# Desktop_Widget_ESP03.net
KiCad netlist of a schematic drawn in EAGLE
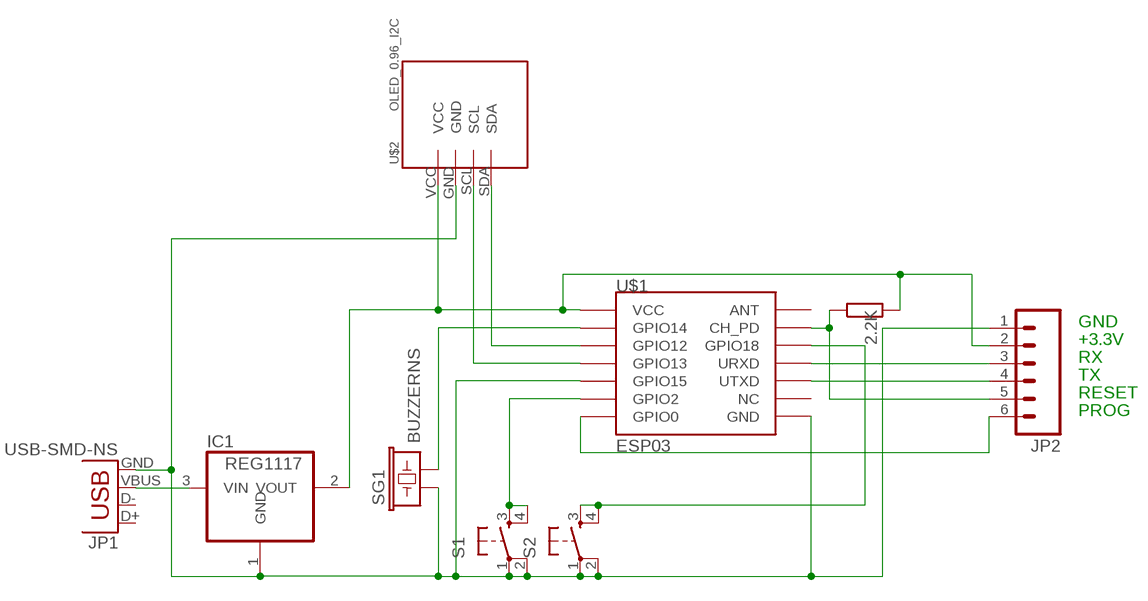
[diagram p0: schematic, sheet 1]

(export (version "E")
  (design (tool "Eeschema 10.0.6"))
  (components
    (comp (ref "IC1")
      (value "REG1117")
      (footprint "eagle-import:SOT223")
      (libsource (lib "eagle-import") (part "REG1117"))
    )
    (comp (ref "JP1")
      (value "USB-SMD-NS")
      (footprint "eagle-import:USB-MINIB-NOSTOP")
      (libsource (lib "eagle-import") (part "USB-SMD-NS"))
    )
    (comp (ref "JP2")
      (value "M06SILK_FEMALE_PTH")
      (footprint "eagle-import:1X06")
      (libsource (lib "eagle-import") (part "M06SILK_FEMALE_PTH"))
    )
    (comp (ref "S1")
      (value "TAC_SWITCHPTH")
      (footprint "eagle-import:TACTILE-PTH")
      (libsource (lib "eagle-import") (part "TAC_SWITCHPTH"))
    )
    (comp (ref "S2")
      (value "TAC_SWITCHPTH")
      (footprint "eagle-import:TACTILE-PTH")
      (libsource (lib "eagle-import") (part "TAC_SWITCHPTH"))
    )
    (comp (ref "SG1")
      (value "BUZZERNS")
      (footprint "eagle-import:BUZZER-12MM-NS")
      (libsource (lib "eagle-import") (part "BUZZERNS"))
    )
    (comp (ref "U$1")
      (value "ESP03")
      (footprint "eagle-import:ESP03")
      (libsource (lib "eagle-import") (part "ESP03"))
    )
    (comp (ref "U$2")
      (value "OLED_0.96_I2C")
      (footprint "eagle-import:OLED_0.96_I2C")
      (libsource (lib "eagle-import") (part "OLED_0.96_I2C"))
    )
  )
  (nets
    (net (code "1") (name "Net-(IC1-GND)") (class "Default")
      (node (ref "IC1") (pin "1") (pinfunction "GND_1") (pintype "power_in"))
      (node (ref "JP1") (pin "GND") (pinfunction "GND_GND") (pintype "bidirectional"))
      (node (ref "JP2") (pin "1") (pinfunction "1_1") (pintype "passive"))
      (node (ref "S1") (pin "1") (pinfunction "1_1") (pintype "passive"))
      (node (ref "S1") (pin "2") (pinfunction "2_2") (pintype "passive"))
      (node (ref "S2") (pin "1") (pinfunction "1_1") (pintype "passive"))
      (node (ref "S2") (pin "2") (pinfunction "2_2") (pintype "passive"))
      (node (ref "SG1") (pin "+") (pinfunction "1_+") (pintype "passive"))
      (node (ref "U$1") (pin "GND") (pinfunction "GND_GND") (pintype "bidirectional"))
      (node (ref "U$1") (pin "GPIO15") (pinfunction "GPIO15_GPIO15") (pintype "bidirectional"))
      (node (ref "U$2") (pin "GND") (pinfunction "GND_GND") (pintype "bidirectional"))
    )
    (net (code "2") (name "Net-(IC1-VOUT)") (class "Default")
      (node (ref "IC1") (pin "2") (pinfunction "VOUT_2") (pintype "output"))
      (node (ref "JP2") (pin "2") (pinfunction "2_2") (pintype "passive"))
      (node (ref "U$1") (pin "VCC") (pinfunction "VCC_VCC") (pintype "bidirectional"))
      (node (ref "U$2") (pin "VCC") (pinfunction "VCC_VCC") (pintype "bidirectional"))
    )
    (net (code "3") (name "Net-(JP2-Pad3)") (class "Default")
      (node (ref "JP2") (pin "3") (pinfunction "3_3") (pintype "passive"))
      (node (ref "U$1") (pin "URXD") (pinfunction "URXD_URXD") (pintype "bidirectional"))
    )
    (net (code "4") (name "Net-(JP2-Pad4)") (class "Default")
      (node (ref "JP2") (pin "4") (pinfunction "4_4") (pintype "passive"))
      (node (ref "U$1") (pin "UTXD") (pinfunction "UTXD_UTXD") (pintype "bidirectional"))
    )
    (net (code "5") (name "Net-(JP2-Pad5)") (class "Default")
      (node (ref "JP2") (pin "5") (pinfunction "5_5") (pintype "passive"))
      (node (ref "U$1") (pin "CH_PD") (pinfunction "CH_PD_CH_PD") (pintype "bidirectional"))
    )
    (net (code "6") (name "Net-(JP2-Pad6)") (class "Default")
      (node (ref "JP2") (pin "6") (pinfunction "6_6") (pintype "passive"))
      (node (ref "U$1") (pin "GPIO0") (pinfunction "GPIO0_GPIO0") (pintype "bidirectional"))
    )
    (net (code "7") (name "Net-(S1-Pad3)") (class "Default")
      (node (ref "S1") (pin "3") (pinfunction "3_3") (pintype "passive"))
      (node (ref "S1") (pin "4") (pinfunction "4_4") (pintype "passive"))
      (node (ref "U$1") (pin "GPIO2") (pinfunction "GPIO2_GPIO2") (pintype "bidirectional"))
    )
    (net (code "8") (name "Net-(S2-Pad3)") (class "Default")
      (node (ref "S2") (pin "3") (pinfunction "3_3") (pintype "passive"))
      (node (ref "S2") (pin "4") (pinfunction "4_4") (pintype "passive"))
      (node (ref "U$1") (pin "GPIO18") (pinfunction "GPIO18_GPIO18") (pintype "bidirectional"))
    )
    (net (code "9") (name "Net-(SG1-2)") (class "Default")
      (node (ref "SG1") (pin "-") (pinfunction "2_-") (pintype "passive"))
      (node (ref "U$1") (pin "GPIO14") (pinfunction "GPIO14_GPIO14") (pintype "bidirectional"))
    )
    (net (code "10") (name "Net-(U$1-PadGPIO12)") (class "Default")
      (node (ref "U$1") (pin "GPIO12") (pinfunction "GPIO12_GPIO12") (pintype "bidirectional"))
      (node (ref "U$2") (pin "SDA") (pinfunction "SDA_SDA") (pintype "bidirectional"))
    )
    (net (code "11") (name "Net-(U$1-PadGPIO13)") (class "Default")
      (node (ref "U$1") (pin "GPIO13") (pinfunction "GPIO13_GPIO13") (pintype "bidirectional"))
      (node (ref "U$2") (pin "SCL") (pinfunction "SCL_SCL") (pintype "bidirectional"))
    )
    (net (code "12") (name "unconnected-(IC1-VIN-Pad3)") (class "Default")
      (node (ref "IC1") (pin "3") (pinfunction "VIN_3") (pintype "input"))
    )
    (net (code "13") (name "unconnected-(JP1-PadD+)") (class "Default")
      (node (ref "JP1") (pin "D+") (pinfunction "D+_D+") (pintype "bidirectional"))
    )
    (net (code "14") (name "unconnected-(JP1-PadD-)") (class "Default")
      (node (ref "JP1") (pin "D-") (pinfunction "D-_D-") (pintype "bidirectional"))
    )
    (net (code "15") (name "unconnected-(JP1-PadVBUS)") (class "Default")
      (node (ref "JP1") (pin "VBUS") (pinfunction "VBUS_VBUS") (pintype "bidirectional"))
    )
    (net (code "16") (name "unconnected-(U$1-PadANT)") (class "Default")
      (node (ref "U$1") (pin "ANT") (pinfunction "ANT_ANT") (pintype "bidirectional"))
    )
    (net (code "17") (name "unconnected-(U$1-PadNC)") (class "Default")
      (node (ref "U$1") (pin "NC") (pinfunction "NC_NC") (pintype "bidirectional"))
    )
  )
)
